# MiSTerDualshock.net
KiCad netlist of a schematic drawn in EAGLE
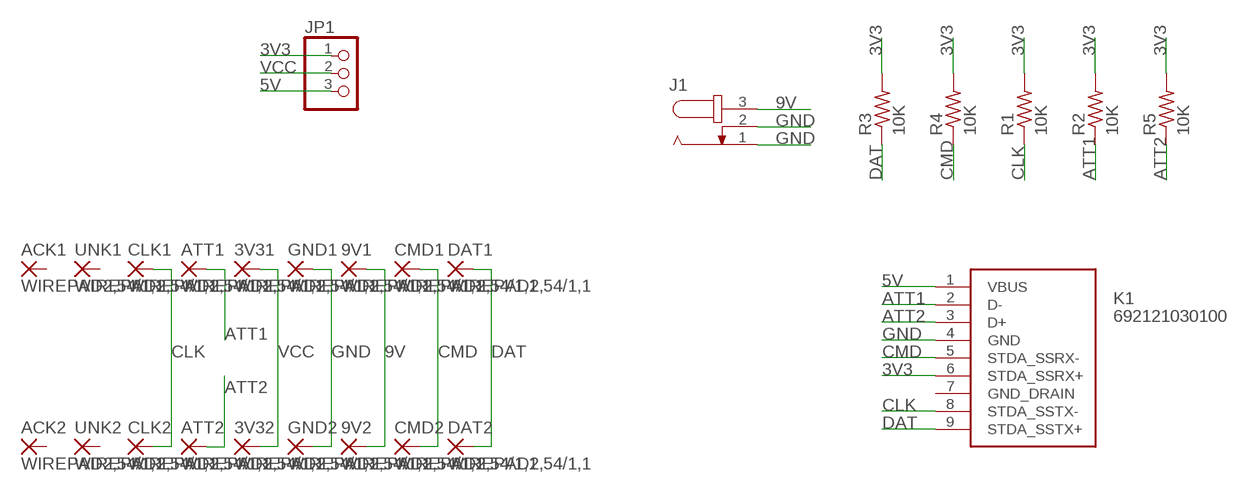
[diagram p0: schematic, sheet 1]

(export (version "E")
  (design (tool "Eeschema 10.0.6"))
  (components
    (comp (ref "3V31")
      (value "WIREPAD2,54/1,1")
      (footprint "eagle-import:2,54_1,1")
      (libsource (lib "eagle-import") (part "WIREPAD2,54/1,1"))
    )
    (comp (ref "3V32")
      (value "WIREPAD2,54/1,1")
      (footprint "eagle-import:2,54_1,1")
      (libsource (lib "eagle-import") (part "WIREPAD2,54/1,1"))
    )
    (comp (ref "9V1")
      (value "WIREPAD2,54/1,1")
      (footprint "eagle-import:2,54_1,1")
      (libsource (lib "eagle-import") (part "WIREPAD2,54/1,1"))
    )
    (comp (ref "9V2")
      (value "WIREPAD2,54/1,1")
      (footprint "eagle-import:2,54_1,1")
      (libsource (lib "eagle-import") (part "WIREPAD2,54/1,1"))
    )
    (comp (ref "ACK1")
      (value "WIREPAD2,54/1,1")
      (footprint "eagle-import:2,54_1,1")
      (libsource (lib "eagle-import") (part "WIREPAD2,54/1,1"))
    )
    (comp (ref "ACK2")
      (value "WIREPAD2,54/1,1")
      (footprint "eagle-import:2,54_1,1")
      (libsource (lib "eagle-import") (part "WIREPAD2,54/1,1"))
    )
    (comp (ref "ATT1")
      (value "WIREPAD2,54/1,1")
      (footprint "eagle-import:2,54_1,1")
      (libsource (lib "eagle-import") (part "WIREPAD2,54/1,1"))
    )
    (comp (ref "ATT2")
      (value "WIREPAD2,54/1,1")
      (footprint "eagle-import:2,54_1,1")
      (libsource (lib "eagle-import") (part "WIREPAD2,54/1,1"))
    )
    (comp (ref "CLK1")
      (value "WIREPAD2,54/1,1")
      (footprint "eagle-import:2,54_1,1")
      (libsource (lib "eagle-import") (part "WIREPAD2,54/1,1"))
    )
    (comp (ref "CLK2")
      (value "WIREPAD2,54/1,1")
      (footprint "eagle-import:2,54_1,1")
      (libsource (lib "eagle-import") (part "WIREPAD2,54/1,1"))
    )
    (comp (ref "CMD1")
      (value "WIREPAD2,54/1,1")
      (footprint "eagle-import:2,54_1,1")
      (libsource (lib "eagle-import") (part "WIREPAD2,54/1,1"))
    )
    (comp (ref "CMD2")
      (value "WIREPAD2,54/1,1")
      (footprint "eagle-import:2,54_1,1")
      (libsource (lib "eagle-import") (part "WIREPAD2,54/1,1"))
    )
    (comp (ref "DAT1")
      (value "WIREPAD2,54/1,1")
      (footprint "eagle-import:2,54_1,1")
      (libsource (lib "eagle-import") (part "WIREPAD2,54/1,1"))
    )
    (comp (ref "DAT2")
      (value "WIREPAD2,54/1,1")
      (footprint "eagle-import:2,54_1,1")
      (libsource (lib "eagle-import") (part "WIREPAD2,54/1,1"))
    )
    (comp (ref "GND1")
      (value "WIREPAD2,54/1,1")
      (footprint "eagle-import:2,54_1,1")
      (libsource (lib "eagle-import") (part "WIREPAD2,54/1,1"))
    )
    (comp (ref "GND2")
      (value "WIREPAD2,54/1,1")
      (footprint "eagle-import:2,54_1,1")
      (libsource (lib "eagle-import") (part "WIREPAD2,54/1,1"))
    )
    (comp (ref "J1")
      (value "JACK-PLUG1")
      (footprint "eagle-import:SPC4078")
      (libsource (lib "eagle-import") (part "JACK-PLUG1"))
    )
    (comp (ref "JP1")
      (value "PINHD-1X3")
      (footprint "eagle-import:1X03")
      (libsource (lib "eagle-import") (part "PINHD-1X3"))
    )
    (comp (ref "K1")
      (value "692121030100")
      (footprint "eagle-import:692121030100")
      (libsource (lib "eagle-import") (part "692121030100"))
    )
    (comp (ref "R1")
      (value "10K")
      (footprint "eagle-import:0207_10")
      (libsource (lib "eagle-import") (part "R-US_0207/10"))
    )
    (comp (ref "R2")
      (value "10K")
      (footprint "eagle-import:0207_10")
      (libsource (lib "eagle-import") (part "R-US_0207/10"))
    )
    (comp (ref "R3")
      (value "10K")
      (footprint "eagle-import:0207_10")
      (libsource (lib "eagle-import") (part "R-US_0207/10"))
    )
    (comp (ref "R4")
      (value "10K")
      (footprint "eagle-import:0207_10")
      (libsource (lib "eagle-import") (part "R-US_0207/10"))
    )
    (comp (ref "R5")
      (value "10K")
      (footprint "eagle-import:0207_10")
      (libsource (lib "eagle-import") (part "R-US_0207/10"))
    )
    (comp (ref "UNK1")
      (value "WIREPAD2,54/1,1")
      (footprint "eagle-import:2,54_1,1")
      (libsource (lib "eagle-import") (part "WIREPAD2,54/1,1"))
    )
    (comp (ref "UNK2")
      (value "WIREPAD2,54/1,1")
      (footprint "eagle-import:2,54_1,1")
      (libsource (lib "eagle-import") (part "WIREPAD2,54/1,1"))
    )
  )
  (nets
    (net (code "1") (name "/3V3") (class "Default")
      (node (ref "JP1") (pin "1") (pinfunction "1_1") (pintype "passive"))
      (node (ref "K1") (pin "6") (pinfunction "STDA_SSRX+_6") (pintype "bidirectional"))
      (node (ref "R1") (pin "2") (pinfunction "2_2") (pintype "passive"))
      (node (ref "R2") (pin "2") (pinfunction "2_2") (pintype "passive"))
      (node (ref "R3") (pin "2") (pinfunction "2_2") (pintype "passive"))
      (node (ref "R4") (pin "2") (pinfunction "2_2") (pintype "passive"))
      (node (ref "R5") (pin "2") (pinfunction "2_2") (pintype "passive"))
    )
    (net (code "2") (name "/5V") (class "Default")
      (node (ref "JP1") (pin "3") (pinfunction "3_3") (pintype "passive"))
      (node (ref "K1") (pin "1") (pinfunction "VBUS_1") (pintype "bidirectional"))
    )
    (net (code "3") (name "/9V") (class "Default")
      (node (ref "9V1") (pin "1") (pinfunction "P_1") (pintype "passive"))
      (node (ref "9V2") (pin "1") (pinfunction "P_1") (pintype "passive"))
      (node (ref "J1") (pin "3") (pinfunction "3_3") (pintype "passive"))
    )
    (net (code "4") (name "/ATT1") (class "Default")
      (node (ref "ATT1") (pin "1") (pinfunction "P_1") (pintype "passive"))
      (node (ref "K1") (pin "2") (pinfunction "D-_2") (pintype "bidirectional"))
      (node (ref "R2") (pin "1") (pinfunction "1_1") (pintype "passive"))
    )
    (net (code "5") (name "/ATT2") (class "Default")
      (node (ref "ATT2") (pin "1") (pinfunction "P_1") (pintype "passive"))
      (node (ref "K1") (pin "3") (pinfunction "D+_3") (pintype "bidirectional"))
      (node (ref "R5") (pin "1") (pinfunction "1_1") (pintype "passive"))
    )
    (net (code "6") (name "/CLK") (class "Default")
      (node (ref "CLK1") (pin "1") (pinfunction "P_1") (pintype "passive"))
      (node (ref "CLK2") (pin "1") (pinfunction "P_1") (pintype "passive"))
      (node (ref "K1") (pin "8") (pinfunction "STDA_SSTX-_8") (pintype "bidirectional"))
      (node (ref "R1") (pin "1") (pinfunction "1_1") (pintype "passive"))
    )
    (net (code "7") (name "/CMD") (class "Default")
      (node (ref "CMD1") (pin "1") (pinfunction "P_1") (pintype "passive"))
      (node (ref "CMD2") (pin "1") (pinfunction "P_1") (pintype "passive"))
      (node (ref "K1") (pin "5") (pinfunction "STDA_SSRX-_5") (pintype "bidirectional"))
      (node (ref "R4") (pin "1") (pinfunction "1_1") (pintype "passive"))
    )
    (net (code "8") (name "/DAT") (class "Default")
      (node (ref "DAT1") (pin "1") (pinfunction "P_1") (pintype "passive"))
      (node (ref "DAT2") (pin "1") (pinfunction "P_1") (pintype "passive"))
      (node (ref "K1") (pin "9") (pinfunction "STDA_SSTX+_9") (pintype "bidirectional"))
      (node (ref "R3") (pin "1") (pinfunction "1_1") (pintype "passive"))
    )
    (net (code "9") (name "/GND") (class "Default")
      (node (ref "GND1") (pin "1") (pinfunction "P_1") (pintype "passive"))
      (node (ref "GND2") (pin "1") (pinfunction "P_1") (pintype "passive"))
      (node (ref "J1") (pin "1") (pinfunction "1_1") (pintype "passive"))
      (node (ref "J1") (pin "2") (pinfunction "2_2") (pintype "passive"))
      (node (ref "K1") (pin "4") (pinfunction "GND_4") (pintype "bidirectional"))
    )
    (net (code "10") (name "/VCC") (class "Default")
      (node (ref "3V31") (pin "1") (pinfunction "P_1") (pintype "passive"))
      (node (ref "3V32") (pin "1") (pinfunction "P_1") (pintype "passive"))
      (node (ref "JP1") (pin "2") (pinfunction "2_2") (pintype "passive"))
    )
    (net (code "11") (name "unconnected-(ACK1-P-Pad1)") (class "Default")
      (node (ref "ACK1") (pin "1") (pinfunction "P_1") (pintype "passive"))
    )
    (net (code "12") (name "unconnected-(ACK2-P-Pad1)") (class "Default")
      (node (ref "ACK2") (pin "1") (pinfunction "P_1") (pintype "passive"))
    )
    (net (code "13") (name "unconnected-(K1-GND_DRAIN-Pad7)") (class "Default")
      (node (ref "K1") (pin "7") (pinfunction "GND_DRAIN_7") (pintype "bidirectional"))
    )
    (net (code "14") (name "unconnected-(UNK1-P-Pad1)") (class "Default")
      (node (ref "UNK1") (pin "1") (pinfunction "P_1") (pintype "passive"))
    )
    (net (code "15") (name "unconnected-(UNK2-P-Pad1)") (class "Default")
      (node (ref "UNK2") (pin "1") (pinfunction "P_1") (pintype "passive"))
    )
  )
)
